# input_amp_w_gp.net
KiCad netlist of a schematic drawn in EAGLE
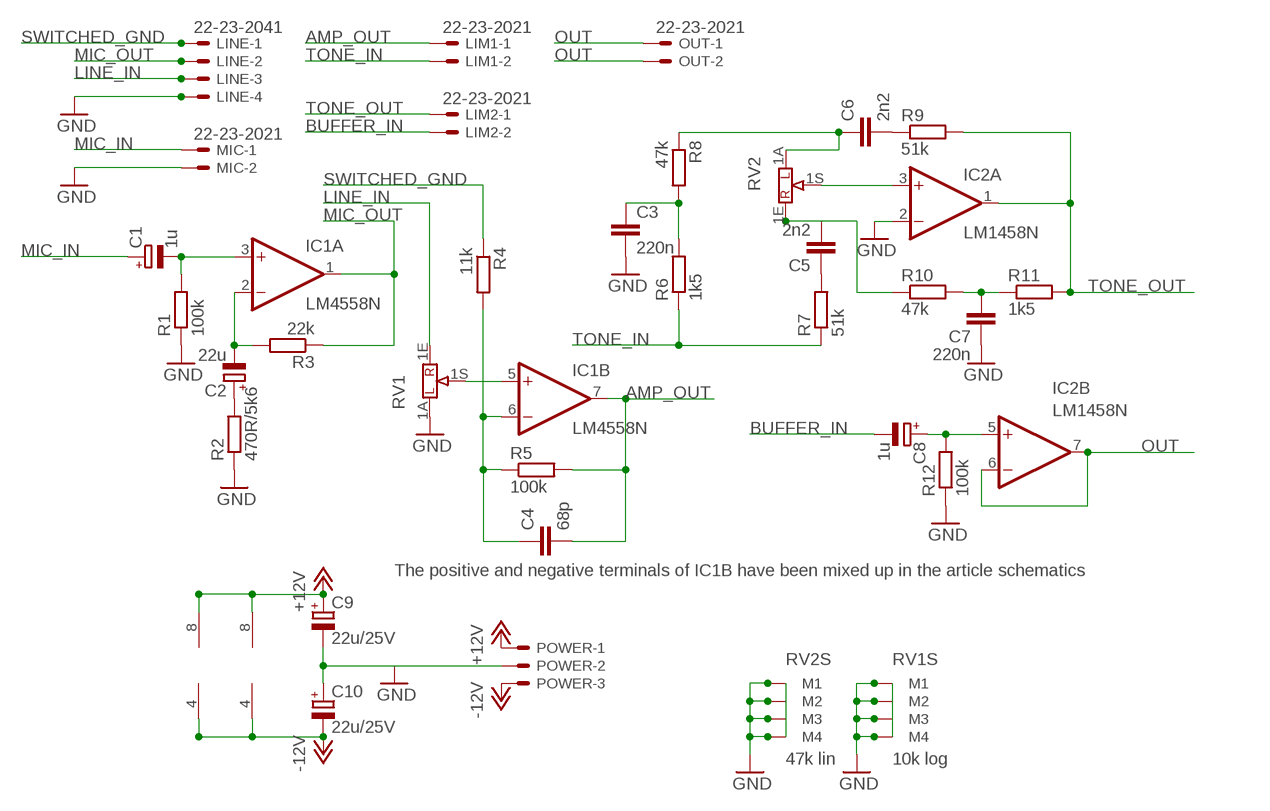
[diagram p0: schematic, sheet 1]

(export (version "E")
  (design (tool "Eeschema 10.0.6"))
  (components
    (comp (ref "C1")
      (value "1u")
      (footprint "eagle-import:E2,5-5")
      (libsource (lib "eagle-import") (part "CPOL-EUE2.5-5"))
    )
    (comp (ref "C2")
      (value "22u")
      (footprint "eagle-import:E2,5-5")
      (libsource (lib "eagle-import") (part "CPOL-EUE2.5-5"))
    )
    (comp (ref "C3")
      (value "220n")
      (footprint "eagle-import:C050-025X075")
      (libsource (lib "eagle-import") (part "C-EU050-025X075"))
    )
    (comp (ref "C4")
      (value "68p")
      (footprint "eagle-import:C025-025X050")
      (libsource (lib "eagle-import") (part "C-EU025-025X050"))
    )
    (comp (ref "C5")
      (value "2n2")
      (footprint "eagle-import:C050-025X075")
      (libsource (lib "eagle-import") (part "C-EU050-025X075"))
    )
    (comp (ref "C6")
      (value "2n2")
      (footprint "eagle-import:C050-025X075")
      (libsource (lib "eagle-import") (part "C-EU050-025X075"))
    )
    (comp (ref "C7")
      (value "220n")
      (footprint "eagle-import:C050-025X075")
      (libsource (lib "eagle-import") (part "C-EU050-025X075"))
    )
    (comp (ref "C8")
      (value "1u")
      (footprint "eagle-import:E2,5-5")
      (libsource (lib "eagle-import") (part "CPOL-EUE2.5-5"))
    )
    (comp (ref "C9")
      (value "22u/25V")
      (footprint "eagle-import:E2,5-5")
      (libsource (lib "eagle-import") (part "CPOL-EUE2.5-5"))
    )
    (comp (ref "C10")
      (value "22u/25V")
      (footprint "eagle-import:E2,5-5")
      (libsource (lib "eagle-import") (part "CPOL-EUE2.5-5"))
    )
    (comp (ref "IC1")
      (value "LM4558N")
      (footprint "eagle-import:DIL08")
      (libsource (lib "eagle-import") (part "4558NLM"))
    )
    (comp (ref "IC2")
      (value "LM1458N")
      (footprint "eagle-import:DIL08")
      (libsource (lib "eagle-import") (part "1458NLM"))
    )
    (comp (ref "LIM1")
      (value "22-23-2021")
      (footprint "eagle-import:22-23-2021")
      (fields (field (name "MF") "MOLEX"))
      (libsource (lib "eagle-import") (part "22-23-2021"))
    )
    (comp (ref "LIM2")
      (value "22-23-2021")
      (footprint "eagle-import:22-23-2021")
      (fields (field (name "MF") "MOLEX"))
      (libsource (lib "eagle-import") (part "22-23-2021"))
    )
    (comp (ref "LINE")
      (value "22-23-2041")
      (footprint "eagle-import:22-23-2041")
      (fields (field (name "MF") "MOLEX"))
      (libsource (lib "eagle-import") (part "22-23-2041"))
    )
    (comp (ref "MIC")
      (value "22-23-2021")
      (footprint "eagle-import:22-23-2021")
      (fields (field (name "MF") "MOLEX"))
      (libsource (lib "eagle-import") (part "22-23-2021"))
    )
    (comp (ref "OUT")
      (value "22-23-2021")
      (footprint "eagle-import:22-23-2021")
      (fields (field (name "MF") "MOLEX"))
      (libsource (lib "eagle-import") (part "22-23-2021"))
    )
    (comp (ref "POWER")
      (value "KK-156-3")
      (footprint "eagle-import:KK-156-3")
      (libsource (lib "eagle-import") (part "KK-156-3"))
    )
    (comp (ref "R1")
      (value "100k")
      (footprint "eagle-import:0207_7")
      (libsource (lib "eagle-import") (part "R-EU_0207/7"))
    )
    (comp (ref "R2")
      (value "470R/5k6")
      (footprint "eagle-import:0207_7")
      (libsource (lib "eagle-import") (part "R-EU_0207/7"))
    )
    (comp (ref "R3")
      (value "22k")
      (footprint "eagle-import:0207_7")
      (libsource (lib "eagle-import") (part "R-EU_0207/7"))
    )
    (comp (ref "R4")
      (value "11k")
      (footprint "eagle-import:0207_7")
      (libsource (lib "eagle-import") (part "R-EU_0207/7"))
    )
    (comp (ref "R5")
      (value "100k")
      (footprint "eagle-import:0207_7")
      (libsource (lib "eagle-import") (part "R-EU_0207/7"))
    )
    (comp (ref "R6")
      (value "1k5")
      (footprint "eagle-import:0207_7")
      (libsource (lib "eagle-import") (part "R-EU_0207/7"))
    )
    (comp (ref "R7")
      (value "51k")
      (footprint "eagle-import:0207_7")
      (libsource (lib "eagle-import") (part "R-EU_0207/7"))
    )
    (comp (ref "R8")
      (value "47k")
      (footprint "eagle-import:0207_7")
      (libsource (lib "eagle-import") (part "R-EU_0207/7"))
    )
    (comp (ref "R9")
      (value "51k")
      (footprint "eagle-import:0207_7")
      (libsource (lib "eagle-import") (part "R-EU_0207/7"))
    )
    (comp (ref "R10")
      (value "47k")
      (footprint "eagle-import:0207_7")
      (libsource (lib "eagle-import") (part "R-EU_0207/7"))
    )
    (comp (ref "R11")
      (value "1k5")
      (footprint "eagle-import:0207_7")
      (libsource (lib "eagle-import") (part "R-EU_0207/7"))
    )
    (comp (ref "R12")
      (value "100k")
      (footprint "eagle-import:0207_7")
      (libsource (lib "eagle-import") (part "R-EU_0207/7"))
    )
    (comp (ref "RV1")
      (value "10k log")
      (footprint "eagle-import:POT16_W_BRACKET")
      (libsource (lib "eagle-import") (part "POT16_W_BRACKET{dblquote}{dblquote}"))
    )
    (comp (ref "RV2")
      (value "47k lin")
      (footprint "eagle-import:POT16_W_BRACKET")
      (libsource (lib "eagle-import") (part "POT16_W_BRACKET{dblquote}{dblquote}"))
    )
  )
  (nets
    (net (code "1") (name "+12V") (class "Default")
      (node (ref "C9") (pin "+") (pinfunction "+_+") (pintype "passive"))
      (node (ref "IC1") (pin "8") (pinfunction "V+_8") (pintype "power_in"))
      (node (ref "IC2") (pin "8") (pinfunction "V+_8") (pintype "power_in"))
      (node (ref "POWER") (pin "1") (pinfunction "S_1") (pintype "passive"))
    )
    (net (code "2") (name "-12V") (class "Default")
      (node (ref "C10") (pin "-") (pinfunction "-_-") (pintype "passive"))
      (node (ref "IC1") (pin "4") (pinfunction "V-_4") (pintype "power_in"))
      (node (ref "IC2") (pin "4") (pinfunction "V-_4") (pintype "power_in"))
      (node (ref "POWER") (pin "3") (pinfunction "S_3") (pintype "passive"))
    )
    (net (code "3") (name "/AMP_OUT") (class "Default")
      (node (ref "C4") (pin "2") (pinfunction "2_2") (pintype "passive"))
      (node (ref "IC1") (pin "7") (pinfunction "OUT_7") (pintype "output"))
      (node (ref "LIM1") (pin "1") (pinfunction "S_1") (pintype "passive"))
      (node (ref "R5") (pin "2") (pinfunction "2_2") (pintype "passive"))
    )
    (net (code "4") (name "/BUFFER_IN") (class "Default")
      (node (ref "C8") (pin "-") (pinfunction "-_-") (pintype "passive"))
      (node (ref "LIM2") (pin "2") (pinfunction "S_2") (pintype "passive"))
    )
    (net (code "5") (name "/LINE_IN") (class "Default")
      (node (ref "LINE") (pin "3") (pinfunction "S_3") (pintype "passive"))
      (node (ref "RV1") (pin "1E") (pinfunction "1E_1E") (pintype "passive"))
    )
    (net (code "6") (name "/MIC_IN") (class "Default")
      (node (ref "C1") (pin "+") (pinfunction "+_+") (pintype "passive"))
      (node (ref "MIC") (pin "1") (pinfunction "S_1") (pintype "passive"))
    )
    (net (code "7") (name "/MIC_OUT") (class "Default")
      (node (ref "IC1") (pin "1") (pinfunction "OUT_1") (pintype "output"))
      (node (ref "LINE") (pin "2") (pinfunction "S_2") (pintype "passive"))
      (node (ref "R3") (pin "1") (pinfunction "1_1") (pintype "passive"))
    )
    (net (code "8") (name "/OUT") (class "Default")
      (node (ref "IC2") (pin "6") (pinfunction "-IN_6") (pintype "input"))
      (node (ref "IC2") (pin "7") (pinfunction "OUT_7") (pintype "output"))
      (node (ref "OUT") (pin "1") (pinfunction "S_1") (pintype "passive"))
      (node (ref "OUT") (pin "2") (pinfunction "S_2") (pintype "passive"))
    )
    (net (code "9") (name "/SWITCHED_GND") (class "Default")
      (node (ref "LINE") (pin "1") (pinfunction "S_1") (pintype "passive"))
      (node (ref "R4") (pin "1") (pinfunction "1_1") (pintype "passive"))
    )
    (net (code "10") (name "/TONE_IN") (class "Default")
      (node (ref "LIM1") (pin "2") (pinfunction "S_2") (pintype "passive"))
      (node (ref "R6") (pin "1") (pinfunction "1_1") (pintype "passive"))
      (node (ref "R7") (pin "1") (pinfunction "1_1") (pintype "passive"))
    )
    (net (code "11") (name "/TONE_OUT") (class "Default")
      (node (ref "IC2") (pin "1") (pinfunction "OUT_1") (pintype "output"))
      (node (ref "LIM2") (pin "1") (pinfunction "S_1") (pintype "passive"))
      (node (ref "R11") (pin "2") (pinfunction "2_2") (pintype "passive"))
      (node (ref "R9") (pin "2") (pinfunction "2_2") (pintype "passive"))
    )
    (net (code "12") (name "GND") (class "Default")
      (node (ref "C10") (pin "+") (pinfunction "+_+") (pintype "passive"))
      (node (ref "C3") (pin "2") (pinfunction "2_2") (pintype "passive"))
      (node (ref "C7") (pin "1") (pinfunction "1_1") (pintype "passive"))
      (node (ref "C9") (pin "-") (pinfunction "-_-") (pintype "passive"))
      (node (ref "IC2") (pin "2") (pinfunction "-IN_2") (pintype "input"))
      (node (ref "LINE") (pin "4") (pinfunction "S_4") (pintype "passive"))
      (node (ref "MIC") (pin "2") (pinfunction "S_2") (pintype "passive"))
      (node (ref "POWER") (pin "2") (pinfunction "S_2") (pintype "passive"))
      (node (ref "R1") (pin "1") (pinfunction "1_1") (pintype "passive"))
      (node (ref "R12") (pin "1") (pinfunction "1_1") (pintype "passive"))
      (node (ref "R2") (pin "1") (pinfunction "1_1") (pintype "passive"))
      (node (ref "RV1") (pin "1A") (pinfunction "1A_1A") (pintype "passive"))
      (node (ref "RV1") (pin "M1") (pinfunction "M1_M1") (pintype "passive"))
      (node (ref "RV1") (pin "M2") (pinfunction "M2_M2") (pintype "passive"))
      (node (ref "RV1") (pin "M3") (pinfunction "M3_M3") (pintype "passive"))
      (node (ref "RV1") (pin "M4") (pinfunction "M4_M4") (pintype "passive"))
      (node (ref "RV2") (pin "M1") (pinfunction "M1_M1") (pintype "passive"))
      (node (ref "RV2") (pin "M2") (pinfunction "M2_M2") (pintype "passive"))
      (node (ref "RV2") (pin "M3") (pinfunction "M3_M3") (pintype "passive"))
      (node (ref "RV2") (pin "M4") (pinfunction "M4_M4") (pintype "passive"))
    )
    (net (code "13") (name "Net-(C2-Pad+)") (class "Default")
      (node (ref "C2") (pin "+") (pinfunction "+_+") (pintype "passive"))
      (node (ref "R2") (pin "2") (pinfunction "2_2") (pintype "passive"))
    )
    (net (code "14") (name "Net-(C3-Pad1)") (class "Default")
      (node (ref "C3") (pin "1") (pinfunction "1_1") (pintype "passive"))
      (node (ref "R6") (pin "2") (pinfunction "2_2") (pintype "passive"))
      (node (ref "R8") (pin "2") (pinfunction "2_2") (pintype "passive"))
    )
    (net (code "15") (name "Net-(C5-Pad1)") (class "Default")
      (node (ref "C5") (pin "1") (pinfunction "1_1") (pintype "passive"))
      (node (ref "R7") (pin "2") (pinfunction "2_2") (pintype "passive"))
    )
    (net (code "16") (name "Net-(C5-Pad2)") (class "Default")
      (node (ref "C5") (pin "2") (pinfunction "2_2") (pintype "passive"))
      (node (ref "R10") (pin "1") (pinfunction "1_1") (pintype "passive"))
      (node (ref "RV2") (pin "1E") (pinfunction "1E_1E") (pintype "passive"))
    )
    (net (code "17") (name "Net-(C6-Pad1)") (class "Default")
      (node (ref "C6") (pin "1") (pinfunction "1_1") (pintype "passive"))
      (node (ref "R8") (pin "1") (pinfunction "1_1") (pintype "passive"))
      (node (ref "RV2") (pin "1A") (pinfunction "1A_1A") (pintype "passive"))
    )
    (net (code "18") (name "Net-(C6-Pad2)") (class "Default")
      (node (ref "C6") (pin "2") (pinfunction "2_2") (pintype "passive"))
      (node (ref "R9") (pin "1") (pinfunction "1_1") (pintype "passive"))
    )
    (net (code "19") (name "Net-(C7-Pad2)") (class "Default")
      (node (ref "C7") (pin "2") (pinfunction "2_2") (pintype "passive"))
      (node (ref "R10") (pin "2") (pinfunction "2_2") (pintype "passive"))
      (node (ref "R11") (pin "1") (pinfunction "1_1") (pintype "passive"))
    )
    (net (code "20") (name "Net-(IC1A-+IN)") (class "Default")
      (node (ref "C1") (pin "-") (pinfunction "-_-") (pintype "passive"))
      (node (ref "IC1") (pin "3") (pinfunction "+IN_3") (pintype "input"))
      (node (ref "R1") (pin "2") (pinfunction "2_2") (pintype "passive"))
    )
    (net (code "21") (name "Net-(IC1A--IN)") (class "Default")
      (node (ref "C2") (pin "-") (pinfunction "-_-") (pintype "passive"))
      (node (ref "IC1") (pin "2") (pinfunction "-IN_2") (pintype "input"))
      (node (ref "R3") (pin "2") (pinfunction "2_2") (pintype "passive"))
    )
    (net (code "22") (name "Net-(IC1B-+IN)") (class "Default")
      (node (ref "IC1") (pin "5") (pinfunction "+IN_5") (pintype "input"))
      (node (ref "RV1") (pin "1S") (pinfunction "1S_1S") (pintype "passive"))
    )
    (net (code "23") (name "Net-(IC1B--IN)") (class "Default")
      (node (ref "C4") (pin "1") (pinfunction "1_1") (pintype "passive"))
      (node (ref "IC1") (pin "6") (pinfunction "-IN_6") (pintype "input"))
      (node (ref "R4") (pin "2") (pinfunction "2_2") (pintype "passive"))
      (node (ref "R5") (pin "1") (pinfunction "1_1") (pintype "passive"))
    )
    (net (code "24") (name "Net-(IC2A-+IN)") (class "Default")
      (node (ref "IC2") (pin "3") (pinfunction "+IN_3") (pintype "input"))
      (node (ref "RV2") (pin "1S") (pinfunction "1S_1S") (pintype "passive"))
    )
    (net (code "25") (name "Net-(IC2B-+IN)") (class "Default")
      (node (ref "C8") (pin "+") (pinfunction "+_+") (pintype "passive"))
      (node (ref "IC2") (pin "5") (pinfunction "+IN_5") (pintype "input"))
      (node (ref "R12") (pin "2") (pinfunction "2_2") (pintype "passive"))
    )
  )
)
